# Carte_Barriere_Optique.net
KiCad netlist of a schematic drawn in Altium Designer
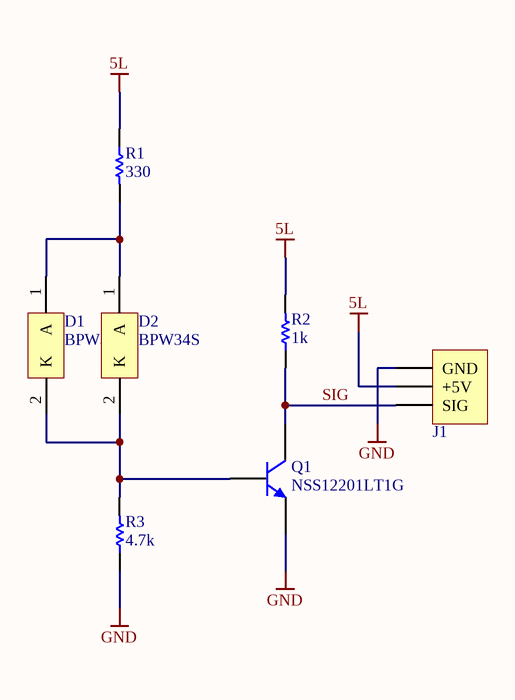
[diagram p0: Carte_Barriere_Optique.SchDoc]

(export (version "E")
  (design (tool "Eeschema 10.0.6"))
  (components
    (comp (ref "D1")
      (value "BPW34")
      (footprint "BPW34")
      (description "PHOTODIODE PIN TOP VIEW 2-DIP")
      (fields (field (name "MANUFACTURER") "OSRAM"))
      (libsource (lib "Optoélectronique") (part "BPW34"))
    )
    (comp (ref "D2")
      (value "BPW34S")
      (footprint "BPW34-S")
      (description "Photodiode 850nm 20ns 120° 2-SMD, Gull Wing")
      (fields (field (name "MANUFACTURER") "OSRAM"))
      (libsource (lib "Optoélectronique") (part "BPW34S"))
    )
    (comp (ref "J1")
      (value "61300311021")
      (footprint "61300311021")
      (description "CONN HEADER 3p horiz. 2.54mm")
      (fields (field (name "MANUFACTURER") "Wurth Electronics Inc."))
      (libsource (lib "Connecteurs") (part "61300311021"))
    )
    (comp (ref "Q1")
      (value "NSS12201LT1G")
      (footprint "SOT-23")
      (description "Bipolar (BJT) Transistor NPN 12V 2A 150MHz 460mW Surface Mount SOT-23-3 (TO-236)")
      (fields (field (name "MANUFACTURER PART NUMBER") "NSS12201LT1G"))
      (libsource (lib "Transistors") (part "NSS12201LT1G"))
    )
    (comp (ref "R1")
      (value "330")
      (footprint "RESC1608X06N")
      (description "RES SMD 330 OHM 1% 1/10W 0603")
      (fields
        (field (name "MANUFACTURER") "Yageo")
        (field (name "MANUFACTURER PART NUMBER") "RC0603FR-07330RL")
      )
      (libsource (lib "Resistance") (part "RC0603FR-07330RL"))
    )
    (comp (ref "R2")
      (value "1k")
      (footprint "RESC1608X06N")
      (description "RES SMD 1K OHM 1% 1/10W 0603")
      (fields
        (field (name "MANUFACTURER") "Yageo")
        (field (name "MANUFACTURER PART NUMBER") "RC0603FR-071KL")
      )
      (libsource (lib "Resistance") (part "RC0603FR-071KL"))
    )
    (comp (ref "R3")
      (value "4.7k")
      (footprint "RESC1005X04N")
      (description "RES SMD 4K7 OHM 1% 1/16W 0402")
      (fields (field (name "POWER") "63mW") (field (name "MANUFACTURER") "Yageo"))
      (libsource (lib "Resistance") (part "RC0402FR-074K7L"))
    )
  )
  (nets
    (net (code "1") (name "/SIG") (class "Default")
      (node (ref "J1") (pin "3") (pinfunction "SIG_3") (pintype "passive"))
      (node (ref "Q1") (pin "3") (pinfunction "C_3") (pintype "passive"))
      (node (ref "R2") (pin "1") (pinfunction "1_1") (pintype "passive"))
    )
    (net (code "2") (name "5L") (class "Default")
      (node (ref "J1") (pin "2") (pinfunction "+5V_2") (pintype "passive"))
      (node (ref "R1") (pin "1") (pinfunction "1_1") (pintype "passive"))
      (node (ref "R2") (pin "2") (pinfunction "2_2") (pintype "passive"))
    )
    (net (code "3") (name "GND") (class "Default")
      (node (ref "J1") (pin "1") (pinfunction "GND_1") (pintype "passive"))
      (node (ref "Q1") (pin "2") (pinfunction "E_2") (pintype "passive"))
      (node (ref "R3") (pin "1") (pinfunction "1_1") (pintype "passive"))
    )
    (net (code "4") (name "Net-(D1-A)") (class "Default")
      (node (ref "D1") (pin "1") (pinfunction "A_1") (pintype "passive"))
      (node (ref "D2") (pin "1") (pinfunction "A_1") (pintype "passive"))
      (node (ref "R1") (pin "2") (pinfunction "2_2") (pintype "passive"))
    )
    (net (code "5") (name "Net-(D1-K)") (class "Default")
      (node (ref "D1") (pin "2") (pinfunction "K_2") (pintype "passive"))
      (node (ref "D2") (pin "2") (pinfunction "K_2") (pintype "passive"))
      (node (ref "Q1") (pin "1") (pinfunction "B_1") (pintype "passive"))
      (node (ref "R3") (pin "2") (pinfunction "2_2") (pintype "passive"))
    )
  )
)
